# rpi_pwrspl_02.net
KiCad netlist of a schematic drawn in EAGLE
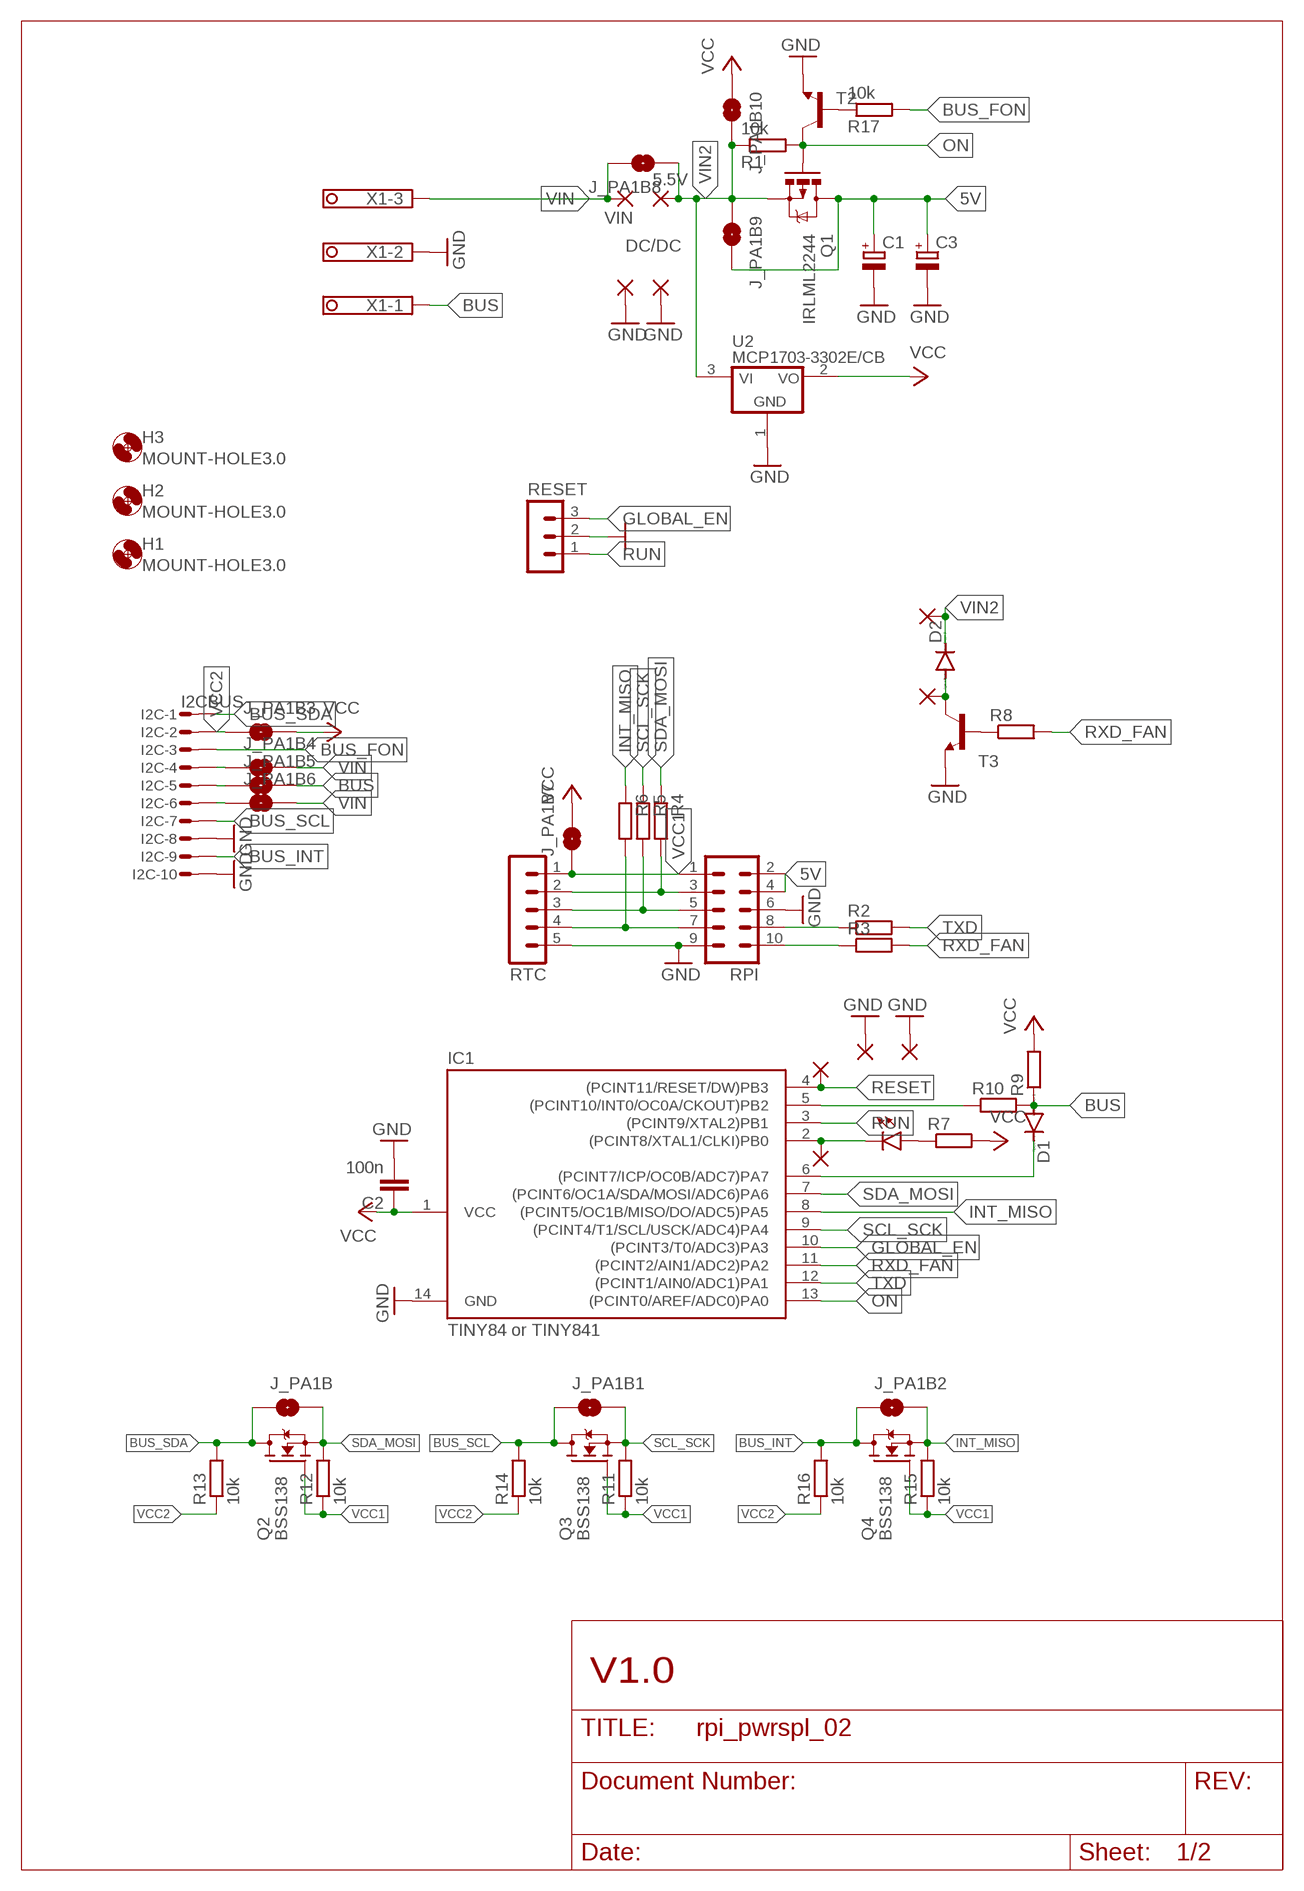
[diagram p0: schematic, sheet 1]

(export (version "E")
  (design (tool "Eeschema 10.0.6"))
  (components
    (comp (ref "5.5V")
      (value "2,54/1,0")
      (footprint "eagle-import:2,54_1,0")
      (libsource (lib "eagle-import") (part "2,54/1,0"))
    )
    (comp (ref "C1")
      (value "CPOL-EUE5-5")
      (footprint "eagle-import:E5-5")
      (libsource (lib "eagle-import") (part "CPOL-EUE5-5"))
    )
    (comp (ref "C2")
      (value "100n")
      (footprint "eagle-import:C0805")
      (libsource (lib "eagle-import") (part "C-EUC0805"))
    )
    (comp (ref "C3")
      (value "CPOL-EU085CS-1AR")
      (footprint "eagle-import:085CS_1AR")
      (libsource (lib "eagle-import") (part "CPOL-EU085CS-1AR"))
    )
    (comp (ref "D1")
      (value "DIODE-MINIMELF")
      (footprint "eagle-import:MINIMELF")
      (libsource (lib "eagle-import") (part "DIODE-MINIMELF"))
    )
    (comp (ref "D2")
      (value "DIODE-MINIMELF")
      (footprint "eagle-import:MINIMELF")
      (libsource (lib "eagle-import") (part "DIODE-MINIMELF"))
    )
    (comp (ref "DW")
      (value "1,6/0,9")
      (footprint "eagle-import:1,6_0,9")
      (libsource (lib "eagle-import") (part "1,6/0,9"))
    )
    (comp (ref "DW1")
      (value "1,6/0,9")
      (footprint "eagle-import:1,6_0,9")
      (libsource (lib "eagle-import") (part "1,6/0,9"))
    )
    (comp (ref "DW2")
      (value "1,6/0,9")
      (footprint "eagle-import:1,6_0,9")
      (libsource (lib "eagle-import") (part "1,6/0,9"))
    )
    (comp (ref "DW3")
      (value "1,6/0,9")
      (footprint "eagle-import:1,6_0,9")
      (libsource (lib "eagle-import") (part "1,6/0,9"))
    )
    (comp (ref "DW4")
      (value "1,6/0,9")
      (footprint "eagle-import:1,6_0,9")
      (libsource (lib "eagle-import") (part "1,6/0,9"))
    )
    (comp (ref "DW5")
      (value "1,6/0,9")
      (footprint "eagle-import:1,6_0,9")
      (libsource (lib "eagle-import") (part "1,6/0,9"))
    )
    (comp (ref "H1")
      (value "MOUNT-HOLE3.0")
      (footprint "eagle-import:3,0")
      (libsource (lib "eagle-import") (part "MOUNT-HOLE3.0"))
    )
    (comp (ref "H2")
      (value "MOUNT-HOLE3.0")
      (footprint "eagle-import:3,0")
      (libsource (lib "eagle-import") (part "MOUNT-HOLE3.0"))
    )
    (comp (ref "H3")
      (value "MOUNT-HOLE3.0")
      (footprint "eagle-import:3,0")
      (libsource (lib "eagle-import") (part "MOUNT-HOLE3.0"))
    )
    (comp (ref "I2C")
      (value "I2CBUS")
      (footprint "eagle-import:MICROMATCH-10SMD")
      (libsource (lib "eagle-import") (part "MICROMATCH-10SMD"))
    )
    (comp (ref "IC1")
      (value "TINY84 or TINY841")
      (footprint "eagle-import:SOIC14")
      (libsource (lib "eagle-import") (part "TINY24/44/84-SSU"))
    )
    (comp (ref "J_PA1B")
      (value "JUMPER-SMT_2_NO_NO-SILK")
      (footprint "eagle-import:SMT-JUMPER_2_NO_NO-SILK")
      (libsource (lib "eagle-import") (part "JUMPER-SMT_2_NO_NO-SILK"))
    )
    (comp (ref "J_PA1B1")
      (value "JUMPER-SMT_2_NO_NO-SILK")
      (footprint "eagle-import:SMT-JUMPER_2_NO_NO-SILK")
      (libsource (lib "eagle-import") (part "JUMPER-SMT_2_NO_NO-SILK"))
    )
    (comp (ref "J_PA1B2")
      (value "JUMPER-SMT_2_NO_NO-SILK")
      (footprint "eagle-import:SMT-JUMPER_2_NO_NO-SILK")
      (libsource (lib "eagle-import") (part "JUMPER-SMT_2_NO_NO-SILK"))
    )
    (comp (ref "J_PA1B3")
      (value "JUMPER-SMT_2_NO_NO-SILK")
      (footprint "eagle-import:SMT-JUMPER_2_NO_NO-SILK")
      (libsource (lib "eagle-import") (part "JUMPER-SMT_2_NO_NO-SILK"))
    )
    (comp (ref "J_PA1B4")
      (value "JUMPER-SMT_2_NO_NO-SILK")
      (footprint "eagle-import:SMT-JUMPER_2_NO_NO-SILK")
      (libsource (lib "eagle-import") (part "JUMPER-SMT_2_NO_NO-SILK"))
    )
    (comp (ref "J_PA1B5")
      (value "JUMPER-SMT_2_NO_NO-SILK")
      (footprint "eagle-import:SMT-JUMPER_2_NO_NO-SILK")
      (libsource (lib "eagle-import") (part "JUMPER-SMT_2_NO_NO-SILK"))
    )
    (comp (ref "J_PA1B6")
      (value "JUMPER-SMT_2_NO_NO-SILK")
      (footprint "eagle-import:SMT-JUMPER_2_NO_NO-SILK")
      (libsource (lib "eagle-import") (part "JUMPER-SMT_2_NO_NO-SILK"))
    )
    (comp (ref "J_PA1B7")
      (value "JUMPER-SMT_2_NO_NO-SILK")
      (footprint "eagle-import:SMT-JUMPER_2_NO_NO-SILK")
      (libsource (lib "eagle-import") (part "JUMPER-SMT_2_NO_NO-SILK"))
    )
    (comp (ref "J_PA1B8")
      (value "JUMPER-SMT_2_NO_NO-SILK")
      (footprint "eagle-import:SMT-JUMPER_2_NO_NO-SILK")
      (libsource (lib "eagle-import") (part "JUMPER-SMT_2_NO_NO-SILK"))
    )
    (comp (ref "J_PA1B9")
      (value "JUMPER-SMT_2_NO_NO-SILK")
      (footprint "eagle-import:SMT-JUMPER_2_NO_NO-SILK")
      (libsource (lib "eagle-import") (part "JUMPER-SMT_2_NO_NO-SILK"))
    )
    (comp (ref "J_PA1B10")
      (value "JUMPER-SMT_2_NO_NO-SILK")
      (footprint "eagle-import:SMT-JUMPER_2_NO_NO-SILK")
      (libsource (lib "eagle-import") (part "JUMPER-SMT_2_NO_NO-SILK"))
    )
    (comp (ref "LED")
      (value "LEDCHIPLED_0805")
      (footprint "eagle-import:CHIPLED_0805")
      (libsource (lib "eagle-import") (part "LEDCHIPLED_0805"))
    )
    (comp (ref "PAD1")
      (value "2,54/1,0")
      (footprint "eagle-import:2,54_1,0")
      (libsource (lib "eagle-import") (part "2,54/1,0"))
    )
    (comp (ref "PAD2")
      (value "2,54/1,0")
      (footprint "eagle-import:2,54_1,0")
      (libsource (lib "eagle-import") (part "2,54/1,0"))
    )
    (comp (ref "Q1")
      (value "IRLML2244")
      (footprint "eagle-import:SOT23-3")
      (libsource (lib "eagle-import") (part "MOSFET-PCHANNELIRLML2244"))
    )
    (comp (ref "Q2")
      (value "BSS138")
      (footprint "eagle-import:SOT23")
      (fields (field (name "MF") "Fairchild"))
      (libsource (lib "eagle-import") (part "BSS138"))
    )
    (comp (ref "Q3")
      (value "BSS138")
      (footprint "eagle-import:SOT23")
      (fields (field (name "MF") "Fairchild"))
      (libsource (lib "eagle-import") (part "BSS138"))
    )
    (comp (ref "Q4")
      (value "BSS138")
      (footprint "eagle-import:SOT23")
      (fields (field (name "MF") "Fairchild"))
      (libsource (lib "eagle-import") (part "BSS138"))
    )
    (comp (ref "R1")
      (value "10k")
      (footprint "eagle-import:R0805")
      (libsource (lib "eagle-import") (part "rcl_334_R-EU_R0805"))
    )
    (comp (ref "R2")
      (value "R-EU_M0805")
      (footprint "eagle-import:M0805")
      (libsource (lib "eagle-import") (part "rcl_334_R-EU_M0805"))
    )
    (comp (ref "R3")
      (value "R-EU_M0805")
      (footprint "eagle-import:M0805")
      (libsource (lib "eagle-import") (part "rcl_334_R-EU_M0805"))
    )
    (comp (ref "R4")
      (value "R-EU_M0805")
      (footprint "eagle-import:M0805")
      (libsource (lib "eagle-import") (part "rcl_334_R-EU_M0805"))
    )
    (comp (ref "R5")
      (value "R-EU_M0805")
      (footprint "eagle-import:M0805")
      (libsource (lib "eagle-import") (part "rcl_334_R-EU_M0805"))
    )
    (comp (ref "R6")
      (value "R-EU_M0805")
      (footprint "eagle-import:M0805")
      (libsource (lib "eagle-import") (part "rcl_334_R-EU_M0805"))
    )
    (comp (ref "R7")
      (value "100")
      (footprint "eagle-import:R0603")
      (libsource (lib "eagle-import") (part "rcl_334_R-EU_R0603"))
    )
    (comp (ref "R8")
      (value "R-EU_M0805")
      (footprint "eagle-import:M0805")
      (libsource (lib "eagle-import") (part "rcl_334_R-EU_M0805"))
    )
    (comp (ref "R9")
      (value "R-EU_M0805")
      (footprint "eagle-import:M0805")
      (libsource (lib "eagle-import") (part "rcl_334_R-EU_M0805"))
    )
    (comp (ref "R10")
      (value "R-EU_M0805")
      (footprint "eagle-import:M0805")
      (libsource (lib "eagle-import") (part "rcl_334_R-EU_M0805"))
    )
    (comp (ref "R11")
      (value "10k")
      (footprint "eagle-import:R0805")
      (libsource (lib "eagle-import") (part "R-EU_R0805"))
    )
    (comp (ref "R12")
      (value "10k")
      (footprint "eagle-import:R0805")
      (libsource (lib "eagle-import") (part "R-EU_R0805"))
    )
    (comp (ref "R13")
      (value "10k")
      (footprint "eagle-import:R0805")
      (libsource (lib "eagle-import") (part "R-EU_R0805"))
    )
    (comp (ref "R14")
      (value "10k")
      (footprint "eagle-import:R0805")
      (libsource (lib "eagle-import") (part "R-EU_R0805"))
    )
    (comp (ref "R15")
      (value "10k")
      (footprint "eagle-import:R0805")
      (libsource (lib "eagle-import") (part "R-EU_R0805"))
    )
    (comp (ref "R16")
      (value "10k")
      (footprint "eagle-import:R0805")
      (libsource (lib "eagle-import") (part "R-EU_R0805"))
    )
    (comp (ref "R17")
      (value "10k")
      (footprint "eagle-import:R0805")
      (libsource (lib "eagle-import") (part "rcl_334_R-EU_R0805"))
    )
    (comp (ref "RESET")
      (value "MA03-1")
      (footprint "eagle-import:MA03-1")
      (libsource (lib "eagle-import") (part "MA03-1"))
    )
    (comp (ref "RPI")
      (value "MA05-2")
      (footprint "eagle-import:MA05-2")
      (libsource (lib "eagle-import") (part "MA05-2"))
    )
    (comp (ref "RTC")
      (value "MA05-1")
      (footprint "eagle-import:MA05-1")
      (libsource (lib "eagle-import") (part "MA05-1"))
    )
    (comp (ref "T2")
      (value "BC817-16-NPN-SOT23-BEC")
      (footprint "eagle-import:SOT23-BEC")
      (libsource (lib "eagle-import") (part "-NPN-SOT23-BECBC817-16"))
    )
    (comp (ref "T3")
      (value "BC817-16-NPN-SOT23-BEC")
      (footprint "eagle-import:SOT23-BEC")
      (libsource (lib "eagle-import") (part "-NPN-SOT23-BECBC817-16"))
    )
    (comp (ref "U2")
      (value "MCP1703-3302E/CB")
      (footprint "eagle-import:SOT23A_MICROCHIP_CB")
      (libsource (lib "eagle-import") (part "MCP170302E/CB-33"))
    )
    (comp (ref "VIN")
      (value "2,54/1,0")
      (footprint "eagle-import:2,54_1,0")
      (libsource (lib "eagle-import") (part "2,54/1,0"))
    )
    (comp (ref "X1")
      (value "1751251")
      (footprint "eagle-import:1751251")
      (libsource (lib "eagle-import") (part "1751251"))
    )
  )
  (nets
    (net (code "1") (name "5V") (class "Default")
      (node (ref "C1") (pin "+") (pinfunction "+_+") (pintype "passive"))
      (node (ref "C3") (pin "+") (pinfunction "+_+") (pintype "passive"))
      (node (ref "J_PA1B9") (pin "2") (pinfunction "2_2") (pintype "passive"))
      (node (ref "Q1") (pin "3") (pinfunction "D_3") (pintype "passive"))
      (node (ref "RPI") (pin "2") (pinfunction "2_2") (pintype "passive"))
      (node (ref "RPI") (pin "4") (pinfunction "4_4") (pintype "passive"))
    )
    (net (code "2") (name "BUS") (class "Default")
      (node (ref "D1") (pin "A") (pinfunction "A_A") (pintype "passive"))
      (node (ref "J_PA1B5") (pin "2") (pinfunction "2_2") (pintype "passive"))
      (node (ref "R10") (pin "2") (pinfunction "2_2") (pintype "passive"))
      (node (ref "R9") (pin "1") (pinfunction "1_1") (pintype "passive"))
      (node (ref "X1") (pin "1") (pinfunction "K_1") (pintype "passive"))
    )
    (net (code "3") (name "BUS_FON") (class "Default")
      (node (ref "I2C") (pin "3") (pinfunction "S_3") (pintype "passive"))
      (node (ref "R17") (pin "2") (pinfunction "2_2") (pintype "passive"))
    )
    (net (code "4") (name "BUS_INT") (class "Default")
      (node (ref "I2C") (pin "9") (pinfunction "S_9") (pintype "passive"))
      (node (ref "J_PA1B2") (pin "1") (pinfunction "1_1") (pintype "passive"))
      (node (ref "Q4") (pin "3") (pinfunction "D_3") (pintype "passive"))
      (node (ref "R16") (pin "2") (pinfunction "2_2") (pintype "passive"))
    )
    (net (code "5") (name "BUS_SCL") (class "Default")
      (node (ref "I2C") (pin "7") (pinfunction "S_7") (pintype "passive"))
      (node (ref "J_PA1B1") (pin "1") (pinfunction "1_1") (pintype "passive"))
      (node (ref "Q3") (pin "3") (pinfunction "D_3") (pintype "passive"))
      (node (ref "R14") (pin "2") (pinfunction "2_2") (pintype "passive"))
    )
    (net (code "6") (name "BUS_SDA") (class "Default")
      (node (ref "I2C") (pin "1") (pinfunction "S_1") (pintype "passive"))
      (node (ref "J_PA1B") (pin "1") (pinfunction "1_1") (pintype "passive"))
      (node (ref "Q2") (pin "3") (pinfunction "D_3") (pintype "passive"))
      (node (ref "R13") (pin "2") (pinfunction "2_2") (pintype "passive"))
    )
    (net (code "7") (name "GLOBAL_EN") (class "Default")
      (node (ref "IC1") (pin "10") (pinfunction "(PCINT3/T0/ADC3)PA3_10") (pintype "bidirectional"))
      (node (ref "RESET") (pin "3") (pinfunction "3_3") (pintype "passive"))
    )
    (net (code "8") (name "GND") (class "Default")
      (node (ref "C1") (pin "-") (pinfunction "-_-") (pintype "passive"))
      (node (ref "C2") (pin "2") (pinfunction "2_2") (pintype "passive"))
      (node (ref "C3") (pin "-") (pinfunction "-_-") (pintype "passive"))
      (node (ref "DW2") (pin "1") (pinfunction "P_1") (pintype "passive"))
      (node (ref "DW3") (pin "1") (pinfunction "P_1") (pintype "passive"))
      (node (ref "I2C") (pin "10") (pinfunction "S_10") (pintype "passive"))
      (node (ref "I2C") (pin "8") (pinfunction "S_8") (pintype "passive"))
      (node (ref "IC1") (pin "14") (pinfunction "GND_14") (pintype "power_in"))
      (node (ref "PAD1") (pin "1") (pinfunction "P_1") (pintype "passive"))
      (node (ref "PAD2") (pin "1") (pinfunction "P_1") (pintype "passive"))
      (node (ref "RESET") (pin "2") (pinfunction "2_2") (pintype "passive"))
      (node (ref "RPI") (pin "6") (pinfunction "6_6") (pintype "passive"))
      (node (ref "RPI") (pin "9") (pinfunction "9_9") (pintype "passive"))
      (node (ref "RTC") (pin "5") (pinfunction "5_5") (pintype "passive"))
      (node (ref "T2") (pin "E") (pinfunction "E_E") (pintype "passive"))
      (node (ref "T3") (pin "E") (pinfunction "E_E") (pintype "passive"))
      (node (ref "U2") (pin "1") (pinfunction "GND_1") (pintype "power_in"))
      (node (ref "X1") (pin "2") (pinfunction "K_2") (pintype "passive"))
    )
    (net (code "9") (name "INT_MISO") (class "Default")
      (node (ref "IC1") (pin "8") (pinfunction "(PCINT5/OC1B/MISO/DO/ADC5)PA5_8") (pintype "bidirectional"))
      (node (ref "J_PA1B2") (pin "2") (pinfunction "2_2") (pintype "passive"))
      (node (ref "Q4") (pin "2") (pinfunction "S_2") (pintype "passive"))
      (node (ref "R15") (pin "2") (pinfunction "2_2") (pintype "passive"))
      (node (ref "R6") (pin "1") (pinfunction "1_1") (pintype "passive"))
    )
    (net (code "10") (name "Net-(DW1-P)") (class "Default")
      (node (ref "DW1") (pin "1") (pinfunction "P_1") (pintype "passive"))
      (node (ref "IC1") (pin "2") (pinfunction "(PCINT8/XTAL1/CLKI)PB0_2") (pintype "bidirectional"))
      (node (ref "LED") (pin "C") (pinfunction "C_C") (pintype "passive"))
    )
    (net (code "11") (name "Net-(DW4-P)") (class "Default")
      (node (ref "D2") (pin "A") (pinfunction "A_A") (pintype "passive"))
      (node (ref "DW4") (pin "1") (pinfunction "P_1") (pintype "passive"))
      (node (ref "T3") (pin "C") (pinfunction "C_C") (pintype "passive"))
    )
    (net (code "12") (name "Net-(I2CE-S)") (class "Default")
      (node (ref "I2C") (pin "4") (pinfunction "S_4") (pintype "passive"))
      (node (ref "J_PA1B4") (pin "1") (pinfunction "1_1") (pintype "passive"))
    )
    (net (code "13") (name "Net-(I2CF-S)") (class "Default")
      (node (ref "I2C") (pin "5") (pinfunction "S_5") (pintype "passive"))
      (node (ref "J_PA1B5") (pin "1") (pinfunction "1_1") (pintype "passive"))
    )
    (net (code "14") (name "Net-(I2CG-S)") (class "Default")
      (node (ref "I2C") (pin "6") (pinfunction "S_6") (pintype "passive"))
      (node (ref "J_PA1B6") (pin "1") (pinfunction "1_1") (pintype "passive"))
    )
    (net (code "15") (name "Net-(IC1-(PCINT7{slash}ICP{slash}OC0B{slash}ADC7)PA7)") (class "Default")
      (node (ref "D1") (pin "C") (pinfunction "C_C") (pintype "passive"))
      (node (ref "IC1") (pin "6") (pinfunction "(PCINT7/ICP/OC0B/ADC7)PA7_6") (pintype "bidirectional"))
    )
    (net (code "16") (name "Net-(IC1-(PCINT10{slash}INT0{slash}OC0A{slash}CKOUT)PB2)") (class "Default")
      (node (ref "IC1") (pin "5") (pinfunction "(PCINT10/INT0/OC0A/CKOUT)PB2_5") (pintype "bidirectional"))
      (node (ref "R10") (pin "1") (pinfunction "1_1") (pintype "passive"))
    )
    (net (code "17") (name "Net-(LED-PadA)") (class "Default")
      (node (ref "LED") (pin "A") (pinfunction "A_A") (pintype "passive"))
      (node (ref "R7") (pin "1") (pinfunction "1_1") (pintype "passive"))
    )
    (net (code "18") (name "Net-(R2-Pad1)") (class "Default")
      (node (ref "R2") (pin "1") (pinfunction "1_1") (pintype "passive"))
      (node (ref "RPI") (pin "8") (pinfunction "8_8") (pintype "passive"))
    )
    (net (code "19") (name "Net-(R3-Pad1)") (class "Default")
      (node (ref "R3") (pin "1") (pinfunction "1_1") (pintype "passive"))
      (node (ref "RPI") (pin "10") (pinfunction "10_10") (pintype "passive"))
    )
    (net (code "20") (name "Net-(R4-Pad2)") (class "Default")
      (node (ref "R4") (pin "2") (pinfunction "2_2") (pintype "passive"))
      (node (ref "RPI") (pin "3") (pinfunction "3_3") (pintype "passive"))
      (node (ref "RTC") (pin "2") (pinfunction "2_2") (pintype "passive"))
    )
    (net (code "21") (name "Net-(R5-Pad2)") (class "Default")
      (node (ref "R5") (pin "2") (pinfunction "2_2") (pintype "passive"))
      (node (ref "RPI") (pin "5") (pinfunction "5_5") (pintype "passive"))
      (node (ref "RTC") (pin "3") (pinfunction "3_3") (pintype "passive"))
    )
    (net (code "22") (name "Net-(R6-Pad2)") (class "Default")
      (node (ref "R6") (pin "2") (pinfunction "2_2") (pintype "passive"))
      (node (ref "RPI") (pin "7") (pinfunction "7_7") (pintype "passive"))
      (node (ref "RTC") (pin "4") (pinfunction "4_4") (pintype "passive"))
    )
    (net (code "23") (name "Net-(R8-Pad1)") (class "Default")
      (node (ref "R8") (pin "1") (pinfunction "1_1") (pintype "passive"))
      (node (ref "T3") (pin "B") (pinfunction "B_B") (pintype "passive"))
    )
    (net (code "24") (name "Net-(R17-Pad1)") (class "Default")
      (node (ref "R17") (pin "1") (pinfunction "1_1") (pintype "passive"))
      (node (ref "T2") (pin "B") (pinfunction "B_B") (pintype "passive"))
    )
    (net (code "25") (name "ON") (class "Default")
      (node (ref "IC1") (pin "13") (pinfunction "(PCINT0/AREF/ADC0)PA0_13") (pintype "bidirectional"))
      (node (ref "Q1") (pin "1") (pinfunction "G_1") (pintype "passive"))
      (node (ref "R1") (pin "2") (pinfunction "2_2") (pintype "passive"))
      (node (ref "T2") (pin "C") (pinfunction "C_C") (pintype "passive"))
    )
    (net (code "26") (name "RESET") (class "Default")
      (node (ref "DW") (pin "1") (pinfunction "P_1") (pintype "passive"))
      (node (ref "IC1") (pin "4") (pinfunction "(PCINT11/RESET/DW)PB3_4") (pintype "bidirectional"))
    )
    (net (code "27") (name "RUN") (class "Default")
      (node (ref "IC1") (pin "3") (pinfunction "(PCINT9/XTAL2)PB1_3") (pintype "bidirectional"))
      (node (ref "RESET") (pin "1") (pinfunction "1_1") (pintype "passive"))
    )
    (net (code "28") (name "RXD_FAN") (class "Default")
      (node (ref "IC1") (pin "11") (pinfunction "(PCINT2/AIN1/ADC2)PA2_11") (pintype "bidirectional"))
      (node (ref "R3") (pin "2") (pinfunction "2_2") (pintype "passive"))
      (node (ref "R8") (pin "2") (pinfunction "2_2") (pintype "passive"))
    )
    (net (code "29") (name "SCL_SCK") (class "Default")
      (node (ref "IC1") (pin "9") (pinfunction "(PCINT4/T1/SCL/USCK/ADC4)PA4_9") (pintype "bidirectional"))
      (node (ref "J_PA1B1") (pin "2") (pinfunction "2_2") (pintype "passive"))
      (node (ref "Q3") (pin "2") (pinfunction "S_2") (pintype "passive"))
      (node (ref "R11") (pin "2") (pinfunction "2_2") (pintype "passive"))
      (node (ref "R5") (pin "1") (pinfunction "1_1") (pintype "passive"))
    )
    (net (code "30") (name "SDA_MOSI") (class "Default")
      (node (ref "IC1") (pin "7") (pinfunction "(PCINT6/OC1A/SDA/MOSI/ADC6)PA6_7") (pintype "bidirectional"))
      (node (ref "J_PA1B") (pin "2") (pinfunction "2_2") (pintype "passive"))
      (node (ref "Q2") (pin "2") (pinfunction "S_2") (pintype "passive"))
      (node (ref "R12") (pin "2") (pinfunction "2_2") (pintype "passive"))
      (node (ref "R4") (pin "1") (pinfunction "1_1") (pintype "passive"))
    )
    (net (code "31") (name "TXD") (class "Default")
      (node (ref "IC1") (pin "12") (pinfunction "(PCINT1/AIN0/ADC1)PA1_12") (pintype "bidirectional"))
      (node (ref "R2") (pin "2") (pinfunction "2_2") (pintype "passive"))
    )
    (net (code "32") (name "VCC") (class "Default")
      (node (ref "C2") (pin "1") (pinfunction "1_1") (pintype "passive"))
      (node (ref "IC1") (pin "1") (pinfunction "VCC_1") (pintype "power_in"))
      (node (ref "J_PA1B10") (pin "1") (pinfunction "1_1") (pintype "passive"))
      (node (ref "J_PA1B3") (pin "2") (pinfunction "2_2") (pintype "passive"))
      (node (ref "J_PA1B7") (pin "2") (pinfunction "2_2") (pintype "passive"))
      (node (ref "R7") (pin "2") (pinfunction "2_2") (pintype "passive"))
      (node (ref "R9") (pin "2") (pinfunction "2_2") (pintype "passive"))
      (node (ref "U2") (pin "2") (pinfunction "VO_2") (pintype "passive"))
    )
    (net (code "33") (name "VCC1") (class "Default")
      (node (ref "J_PA1B7") (pin "1") (pinfunction "1_1") (pintype "passive"))
      (node (ref "Q2") (pin "1") (pinfunction "G_1") (pintype "passive"))
      (node (ref "Q3") (pin "1") (pinfunction "G_1") (pintype "passive"))
      (node (ref "Q4") (pin "1") (pinfunction "G_1") (pintype "passive"))
      (node (ref "R11") (pin "1") (pinfunction "1_1") (pintype "passive"))
      (node (ref "R12") (pin "1") (pinfunction "1_1") (pintype "passive"))
      (node (ref "R15") (pin "1") (pinfunction "1_1") (pintype "passive"))
      (node (ref "RPI") (pin "1") (pinfunction "1_1") (pintype "passive"))
      (node (ref "RTC") (pin "1") (pinfunction "1_1") (pintype "passive"))
    )
    (net (code "34") (name "VCC2") (class "Default")
      (node (ref "I2C") (pin "2") (pinfunction "S_2") (pintype "passive"))
      (node (ref "J_PA1B3") (pin "1") (pinfunction "1_1") (pintype "passive"))
      (node (ref "R13") (pin "1") (pinfunction "1_1") (pintype "passive"))
      (node (ref "R14") (pin "1") (pinfunction "1_1") (pintype "passive"))
      (node (ref "R16") (pin "1") (pinfunction "1_1") (pintype "passive"))
    )
    (net (code "35") (name "VIN") (class "Default")
      (node (ref "J_PA1B4") (pin "2") (pinfunction "2_2") (pintype "passive"))
      (node (ref "J_PA1B6") (pin "2") (pinfunction "2_2") (pintype "passive"))
      (node (ref "J_PA1B8") (pin "2") (pinfunction "2_2") (pintype "passive"))
      (node (ref "VIN") (pin "1") (pinfunction "P_1") (pintype "passive"))
      (node (ref "X1") (pin "3") (pinfunction "K_3") (pintype "passive"))
    )
    (net (code "36") (name "VIN2") (class "Default")
      (node (ref "5.5V") (pin "1") (pinfunction "P_1") (pintype "passive"))
      (node (ref "D2") (pin "C") (pinfunction "C_C") (pintype "passive"))
      (node (ref "DW5") (pin "1") (pinfunction "P_1") (pintype "passive"))
      (node (ref "J_PA1B10") (pin "2") (pinfunction "2_2") (pintype "passive"))
      (node (ref "J_PA1B8") (pin "1") (pinfunction "1_1") (pintype "passive"))
      (node (ref "J_PA1B9") (pin "1") (pinfunction "1_1") (pintype "passive"))
      (node (ref "Q1") (pin "2") (pinfunction "S_2") (pintype "passive"))
      (node (ref "R1") (pin "1") (pinfunction "1_1") (pintype "passive"))
      (node (ref "U2") (pin "3") (pinfunction "VI_3") (pintype "power_in"))
    )
  )
)
